# Moto_Power_Supply_4x12v_4x5v.net
KiCad netlist of a schematic drawn in Altium Designer
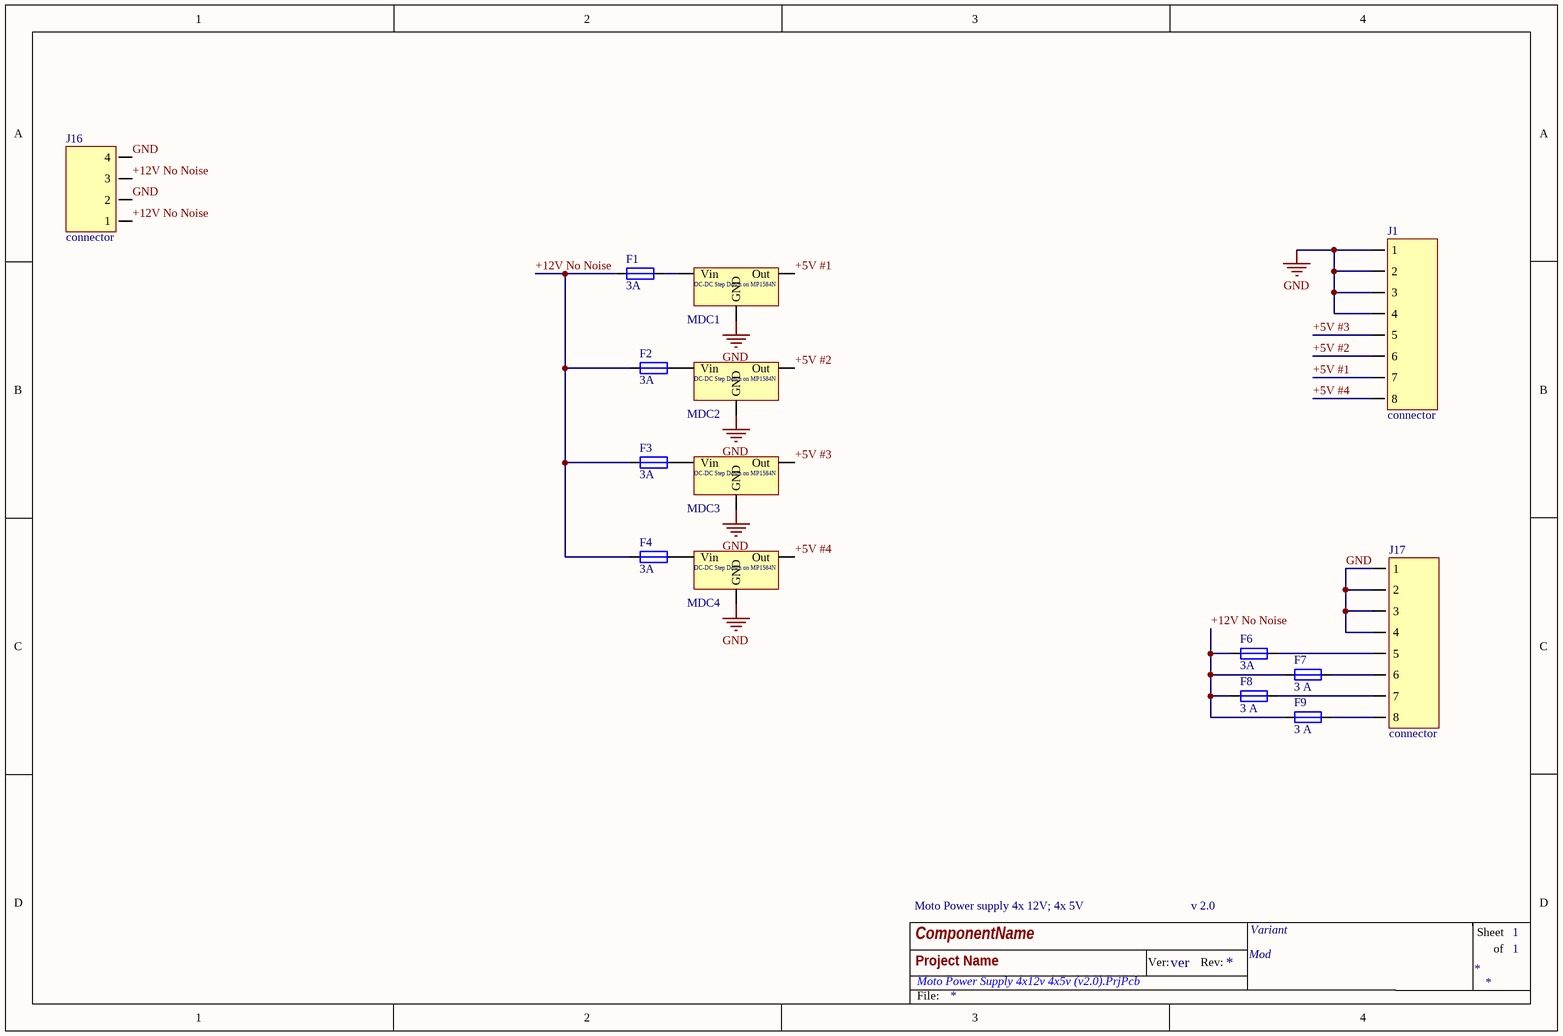
[diagram p0: Moto Power Supply 4x12v 4x5v (v2.0).SchDoc]

(export (version "E")
  (design (tool "Eeschema 10.0.6"))
  (components
    (comp (ref "F1")
      (value "3A")
      (footprint "PassiveComponents:Fuse MF-R300 (3A)")
      (description "Round fuse")
      (libsource (lib "PassiveComponents") (part "Fuse"))
    )
    (comp (ref "F2")
      (value "3A")
      (footprint "PassiveComponents:Fuse MF-R300 (3A)")
      (description "Round fuse")
      (libsource (lib "PassiveComponents") (part "Fuse"))
    )
    (comp (ref "F3")
      (value "3A")
      (footprint "PassiveComponents:Fuse MF-R300 (3A)")
      (description "Round fuse")
      (libsource (lib "PassiveComponents") (part "Fuse"))
    )
    (comp (ref "F4")
      (value "3A")
      (footprint "PassiveComponents:Fuse MF-R300 (3A)")
      (description "Round fuse")
      (libsource (lib "PassiveComponents") (part "Fuse"))
    )
    (comp (ref "F6")
      (value "3A")
      (footprint "PassiveComponents:Fuse MF-R300 (3A)")
      (description "Round fuse")
      (libsource (lib "PassiveComponents") (part "Fuse"))
    )
    (comp (ref "F7")
      (value "3 A")
      (footprint "PassiveComponents:Fuse MF-R300 (3A)")
      (description "Round fuse")
      (libsource (lib "PassiveComponents") (part "Fuse"))
    )
    (comp (ref "F8")
      (value "3 A")
      (footprint "PassiveComponents:Fuse MF-R300 (3A)")
      (description "Round fuse")
      (libsource (lib "PassiveComponents") (part "Fuse"))
    )
    (comp (ref "F9")
      (value "3 A")
      (footprint "PassiveComponents:Fuse MF-R300 (3A)")
      (description "Round fuse")
      (libsource (lib "PassiveComponents") (part "Fuse"))
    )
    (comp (ref "J1")
      (value "connector")
      (footprint "Connector:Molex Mini-Fit Jr - 8Pin V")
      (description "Right, Dbl line, Female")
      (libsource (lib "Connector") (part "Molex Mini-Fit Jr - 8 pin"))
    )
    (comp (ref "J16")
      (value "connector")
      (footprint "Connector:Molex Mini-Fit Jr - 4Pin V")
      (description "Right, Dbl line, Female")
      (libsource (lib "Connector") (part "Molex Mini-Fit Jr - 4 pin"))
    )
    (comp (ref "J17")
      (value "connector")
      (footprint "Connector:Molex Mini-Fit Jr - 8Pin V")
      (description "Right, Dbl line, Female")
      (libsource (lib "Connector") (part "Molex Mini-Fit Jr - 8 pin"))
    )
    (comp (ref "MDC1")
      (value "DC-DC")
      (footprint "Modules:DC-DC_MP1584N (SMALL)")
      (description "DC-DC StepDown")
      (libsource (lib "Modules") (part "DC-DC MP1584N"))
    )
    (comp (ref "MDC2")
      (value "DC-DC")
      (footprint "Modules:DC-DC_MP1584N (SMALL)")
      (description "DC-DC StepDown")
      (libsource (lib "Modules") (part "DC-DC MP1584N"))
    )
    (comp (ref "MDC3")
      (value "DC-DC")
      (footprint "Modules:DC-DC_MP1584N (SMALL)")
      (description "DC-DC StepDown")
      (libsource (lib "Modules") (part "DC-DC MP1584N"))
    )
    (comp (ref "MDC4")
      (value "DC-DC")
      (footprint "Modules:DC-DC_MP1584N (SMALL)")
      (description "DC-DC StepDown")
      (libsource (lib "Modules") (part "DC-DC MP1584N"))
    )
  )
  (nets
    (net (code "1") (name "/+5V #1") (class "Default")
      (node (ref "J1") (pin "7") (pinfunction "7_7") (pintype "passive"))
      (node (ref "MDC1") (pin "OUT") (pinfunction "Out_OUT") (pintype "passive"))
    )
    (net (code "2") (name "/+5V #2") (class "Default")
      (node (ref "J1") (pin "6") (pinfunction "6_6") (pintype "passive"))
      (node (ref "MDC2") (pin "OUT") (pinfunction "Out_OUT") (pintype "passive"))
    )
    (net (code "3") (name "/+5V #3") (class "Default")
      (node (ref "J1") (pin "5") (pinfunction "5_5") (pintype "passive"))
      (node (ref "MDC3") (pin "OUT") (pinfunction "Out_OUT") (pintype "passive"))
    )
    (net (code "4") (name "/+5V #4") (class "Default")
      (node (ref "J1") (pin "8") (pinfunction "8_8") (pintype "passive"))
      (node (ref "MDC4") (pin "OUT") (pinfunction "Out_OUT") (pintype "passive"))
    )
    (net (code "5") (name "/+12V No Noise") (class "Default")
      (node (ref "F1") (pin "2") (pinfunction "2_2") (pintype "passive"))
      (node (ref "F2") (pin "2") (pinfunction "2_2") (pintype "passive"))
      (node (ref "F3") (pin "2") (pinfunction "2_2") (pintype "passive"))
      (node (ref "F4") (pin "2") (pinfunction "2_2") (pintype "passive"))
      (node (ref "F6") (pin "2") (pinfunction "2_2") (pintype "passive"))
      (node (ref "F7") (pin "2") (pinfunction "2_2") (pintype "passive"))
      (node (ref "F8") (pin "2") (pinfunction "2_2") (pintype "passive"))
      (node (ref "F9") (pin "2") (pinfunction "2_2") (pintype "passive"))
      (node (ref "J16") (pin "1") (pinfunction "1_1") (pintype "passive"))
      (node (ref "J16") (pin "3") (pinfunction "3_3") (pintype "passive"))
    )
    (net (code "6") (name "GND") (class "Default")
      (node (ref "J1") (pin "1") (pinfunction "1_1") (pintype "passive"))
      (node (ref "J1") (pin "2") (pinfunction "2_2") (pintype "passive"))
      (node (ref "J1") (pin "3") (pinfunction "3_3") (pintype "passive"))
      (node (ref "J1") (pin "4") (pinfunction "4_4") (pintype "passive"))
      (node (ref "J16") (pin "2") (pinfunction "2_2") (pintype "passive"))
      (node (ref "J16") (pin "4") (pinfunction "4_4") (pintype "passive"))
      (node (ref "J17") (pin "1") (pinfunction "1_1") (pintype "passive"))
      (node (ref "J17") (pin "2") (pinfunction "2_2") (pintype "passive"))
      (node (ref "J17") (pin "3") (pinfunction "3_3") (pintype "passive"))
      (node (ref "J17") (pin "4") (pinfunction "4_4") (pintype "passive"))
      (node (ref "MDC1") (pin "GND") (pinfunction "GND_GND") (pintype "passive"))
      (node (ref "MDC2") (pin "GND") (pinfunction "GND_GND") (pintype "passive"))
      (node (ref "MDC3") (pin "GND") (pinfunction "GND_GND") (pintype "passive"))
      (node (ref "MDC4") (pin "GND") (pinfunction "GND_GND") (pintype "passive"))
    )
    (net (code "7") (name "Net-(F6-Pad1)") (class "Default")
      (node (ref "F6") (pin "1") (pinfunction "1_1") (pintype "passive"))
      (node (ref "J17") (pin "5") (pinfunction "5_5") (pintype "passive"))
    )
    (net (code "8") (name "Net-(F7-Pad1)") (class "Default")
      (node (ref "F7") (pin "1") (pinfunction "1_1") (pintype "passive"))
      (node (ref "J17") (pin "6") (pinfunction "6_6") (pintype "passive"))
    )
    (net (code "9") (name "Net-(F8-Pad1)") (class "Default")
      (node (ref "F8") (pin "1") (pinfunction "1_1") (pintype "passive"))
      (node (ref "J17") (pin "7") (pinfunction "7_7") (pintype "passive"))
    )
    (net (code "10") (name "Net-(F9-Pad1)") (class "Default")
      (node (ref "F9") (pin "1") (pinfunction "1_1") (pintype "passive"))
      (node (ref "J17") (pin "8") (pinfunction "8_8") (pintype "passive"))
    )
    (net (code "11") (name "Net-(MDC1-Vin)") (class "Default")
      (node (ref "F1") (pin "1") (pinfunction "1_1") (pintype "passive"))
      (node (ref "MDC1") (pin "IN") (pinfunction "Vin_IN") (pintype "passive"))
    )
    (net (code "12") (name "Net-(MDC2-Vin)") (class "Default")
      (node (ref "F2") (pin "1") (pinfunction "1_1") (pintype "passive"))
      (node (ref "MDC2") (pin "IN") (pinfunction "Vin_IN") (pintype "passive"))
    )
    (net (code "13") (name "Net-(MDC3-Vin)") (class "Default")
      (node (ref "F3") (pin "1") (pinfunction "1_1") (pintype "passive"))
      (node (ref "MDC3") (pin "IN") (pinfunction "Vin_IN") (pintype "passive"))
    )
    (net (code "14") (name "Net-(MDC4-Vin)") (class "Default")
      (node (ref "F4") (pin "1") (pinfunction "1_1") (pintype "passive"))
      (node (ref "MDC4") (pin "IN") (pinfunction "Vin_IN") (pintype "passive"))
    )
  )
)
